# L293DD.net
KiCad netlist of a schematic drawn in Altium Designer
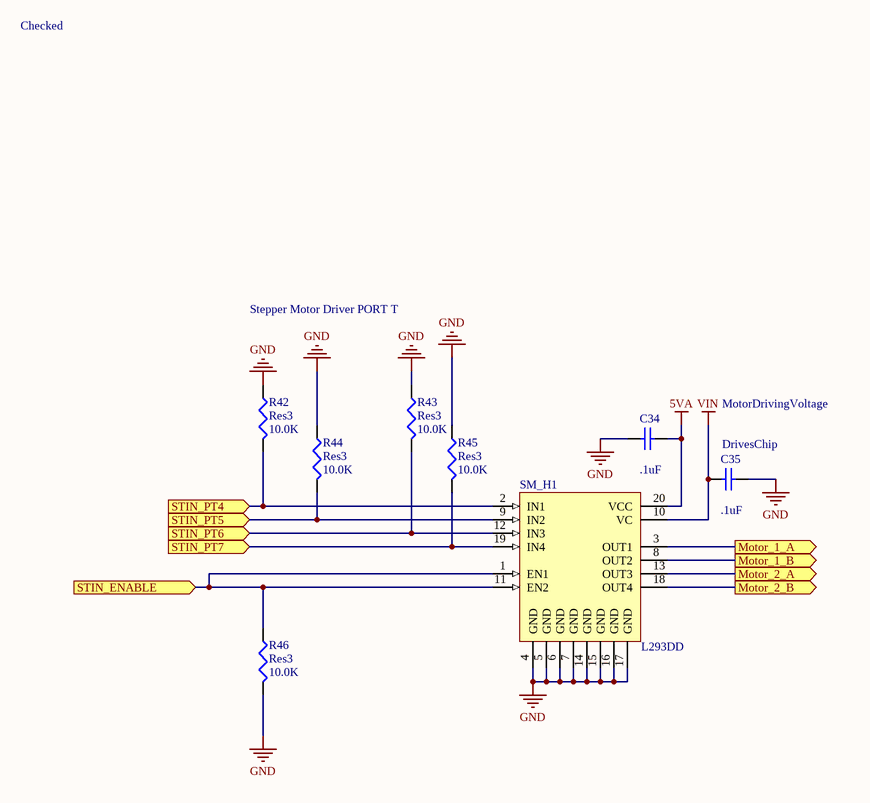
[diagram p0: L293DD.SchDoc]

(export (version "E")
  (design (tool "Eeschema 10.0.6"))
  (components
    (comp (ref "C34")
      (value ".1uF")
      (footprint "CAPC2012X09M")
      (description "CAP CER .1uF 50v X7R 0805")
      (fields (field (name "TOLERANCE") "±20%") (field (name "MPN") "C0805C104M5RACTU"))
      (libsource (lib "esd_library") (part "CAP-X7R-.1uF-50V-±20%"))
    )
    (comp (ref "C35")
      (value ".1uF")
      (footprint "CAPC2012X09M")
      (description "CAP CER .1uF 50v X7R 0805")
      (fields (field (name "TOLERANCE") "±20%") (field (name "MPN") "C0805C104M5RACTU"))
      (libsource (lib "esd_library") (part "CAP-X7R-.1uF-50V-±20%"))
    )
    (comp (ref "R42")
      (value "Res3")
      (footprint "RESC2112X05M")
      (description "RES SMD 10.0K OHM 1% 1/8W 0805")
      (fields (field (name "ALTIUM_VALUE") "10.0K") (field (name "MPN") "CRCW080510K0FKEA"))
      (libsource (lib "esd_library") (part "Resistor_10.0K"))
    )
    (comp (ref "R43")
      (value "Res3")
      (footprint "RESC2112X05M")
      (description "RES SMD 10.0K OHM 1% 1/8W 0805")
      (fields (field (name "ALTIUM_VALUE") "10.0K") (field (name "MPN") "CRCW080510K0FKEA"))
      (libsource (lib "esd_library") (part "Resistor_10.0K"))
    )
    (comp (ref "R44")
      (value "Res3")
      (footprint "RESC2112X05M")
      (description "RES SMD 10.0K OHM 1% 1/8W 0805")
      (fields (field (name "ALTIUM_VALUE") "10.0K") (field (name "MPN") "CRCW080510K0FKEA"))
      (libsource (lib "esd_library") (part "Resistor_10.0K"))
    )
    (comp (ref "R45")
      (value "Res3")
      (footprint "RESC2112X05M")
      (description "RES SMD 10.0K OHM 1% 1/8W 0805")
      (fields (field (name "ALTIUM_VALUE") "10.0K") (field (name "MPN") "CRCW080510K0FKEA"))
      (libsource (lib "esd_library") (part "Resistor_10.0K"))
    )
    (comp (ref "R46")
      (value "Res3")
      (footprint "RESC2112X05M")
      (description "RES SMD 10.0K OHM 1% 1/8W 0805")
      (fields (field (name "ALTIUM_VALUE") "10.0K") (field (name "MPN") "CRCW080510K0FKEA"))
      (libsource (lib "esd_library") (part "Resistor_10.0K"))
    )
    (comp (ref "SM_H1")
      (value "L293DD")
      (footprint "SO20_N")
      (description "Push-Pull Four Channel Driver With Diode")
      (fields (field (name "PUBLISHER") "Altium Limited"))
      (libsource (lib "esd_library") (part "L293DD"))
    )
  )
  (nets
    (net (code "1") (name "/Motor_1_A") (class "Default")
      (node (ref "SM_H1") (pin "3") (pinfunction "OUT1_3") (pintype "tri_state"))
    )
    (net (code "2") (name "/Motor_1_B") (class "Default")
      (node (ref "SM_H1") (pin "8") (pinfunction "OUT2_8") (pintype "tri_state"))
    )
    (net (code "3") (name "/Motor_2_A") (class "Default")
      (node (ref "SM_H1") (pin "13") (pinfunction "OUT3_13") (pintype "tri_state"))
    )
    (net (code "4") (name "/Motor_2_B") (class "Default")
      (node (ref "SM_H1") (pin "18") (pinfunction "OUT4_18") (pintype "tri_state"))
    )
    (net (code "5") (name "/STIN_ENABLE") (class "Default")
      (node (ref "R46") (pin "1") (pinfunction "1_1") (pintype "passive"))
      (node (ref "SM_H1") (pin "1") (pinfunction "EN1_1") (pintype "input"))
      (node (ref "SM_H1") (pin "11") (pinfunction "EN2_11") (pintype "input"))
    )
    (net (code "6") (name "/STIN_PT4") (class "Default")
      (node (ref "R42") (pin "2") (pinfunction "2_2") (pintype "passive"))
      (node (ref "SM_H1") (pin "2") (pinfunction "IN1_2") (pintype "input"))
    )
    (net (code "7") (name "/STIN_PT5") (class "Default")
      (node (ref "R44") (pin "2") (pinfunction "2_2") (pintype "passive"))
      (node (ref "SM_H1") (pin "9") (pinfunction "IN2_9") (pintype "input"))
    )
    (net (code "8") (name "/STIN_PT6") (class "Default")
      (node (ref "R43") (pin "2") (pinfunction "2_2") (pintype "passive"))
      (node (ref "SM_H1") (pin "12") (pinfunction "IN3_12") (pintype "input"))
    )
    (net (code "9") (name "/STIN_PT7") (class "Default")
      (node (ref "R45") (pin "2") (pinfunction "2_2") (pintype "passive"))
      (node (ref "SM_H1") (pin "19") (pinfunction "IN4_19") (pintype "input"))
    )
    (net (code "10") (name "5VA") (class "Default")
      (node (ref "C34") (pin "2") (pinfunction "2_2") (pintype "passive"))
      (node (ref "SM_H1") (pin "20") (pinfunction "VCC_20") (pintype "power_in"))
    )
    (net (code "11") (name "GND") (class "Default")
      (node (ref "C34") (pin "1") (pinfunction "1_1") (pintype "passive"))
      (node (ref "C35") (pin "2") (pinfunction "2_2") (pintype "passive"))
      (node (ref "R42") (pin "1") (pinfunction "1_1") (pintype "passive"))
      (node (ref "R43") (pin "1") (pinfunction "1_1") (pintype "passive"))
      (node (ref "R44") (pin "1") (pinfunction "1_1") (pintype "passive"))
      (node (ref "R45") (pin "1") (pinfunction "1_1") (pintype "passive"))
      (node (ref "R46") (pin "2") (pinfunction "2_2") (pintype "passive"))
      (node (ref "SM_H1") (pin "14") (pinfunction "GND_14") (pintype "power_in"))
      (node (ref "SM_H1") (pin "15") (pinfunction "GND_15") (pintype "power_in"))
      (node (ref "SM_H1") (pin "16") (pinfunction "GND_16") (pintype "power_in"))
      (node (ref "SM_H1") (pin "17") (pinfunction "GND_17") (pintype "power_in"))
      (node (ref "SM_H1") (pin "4") (pinfunction "GND_4") (pintype "power_in"))
      (node (ref "SM_H1") (pin "5") (pinfunction "GND_5") (pintype "power_in"))
      (node (ref "SM_H1") (pin "6") (pinfunction "GND_6") (pintype "power_in"))
      (node (ref "SM_H1") (pin "7") (pinfunction "GND_7") (pintype "power_in"))
    )
    (net (code "12") (name "VIN") (class "Default")
      (node (ref "C35") (pin "1") (pinfunction "1_1") (pintype "passive"))
      (node (ref "SM_H1") (pin "10") (pinfunction "VC_10") (pintype "power_in"))
    )
  )
)
